# Payload.net
KiCad netlist of a schematic drawn in EAGLE
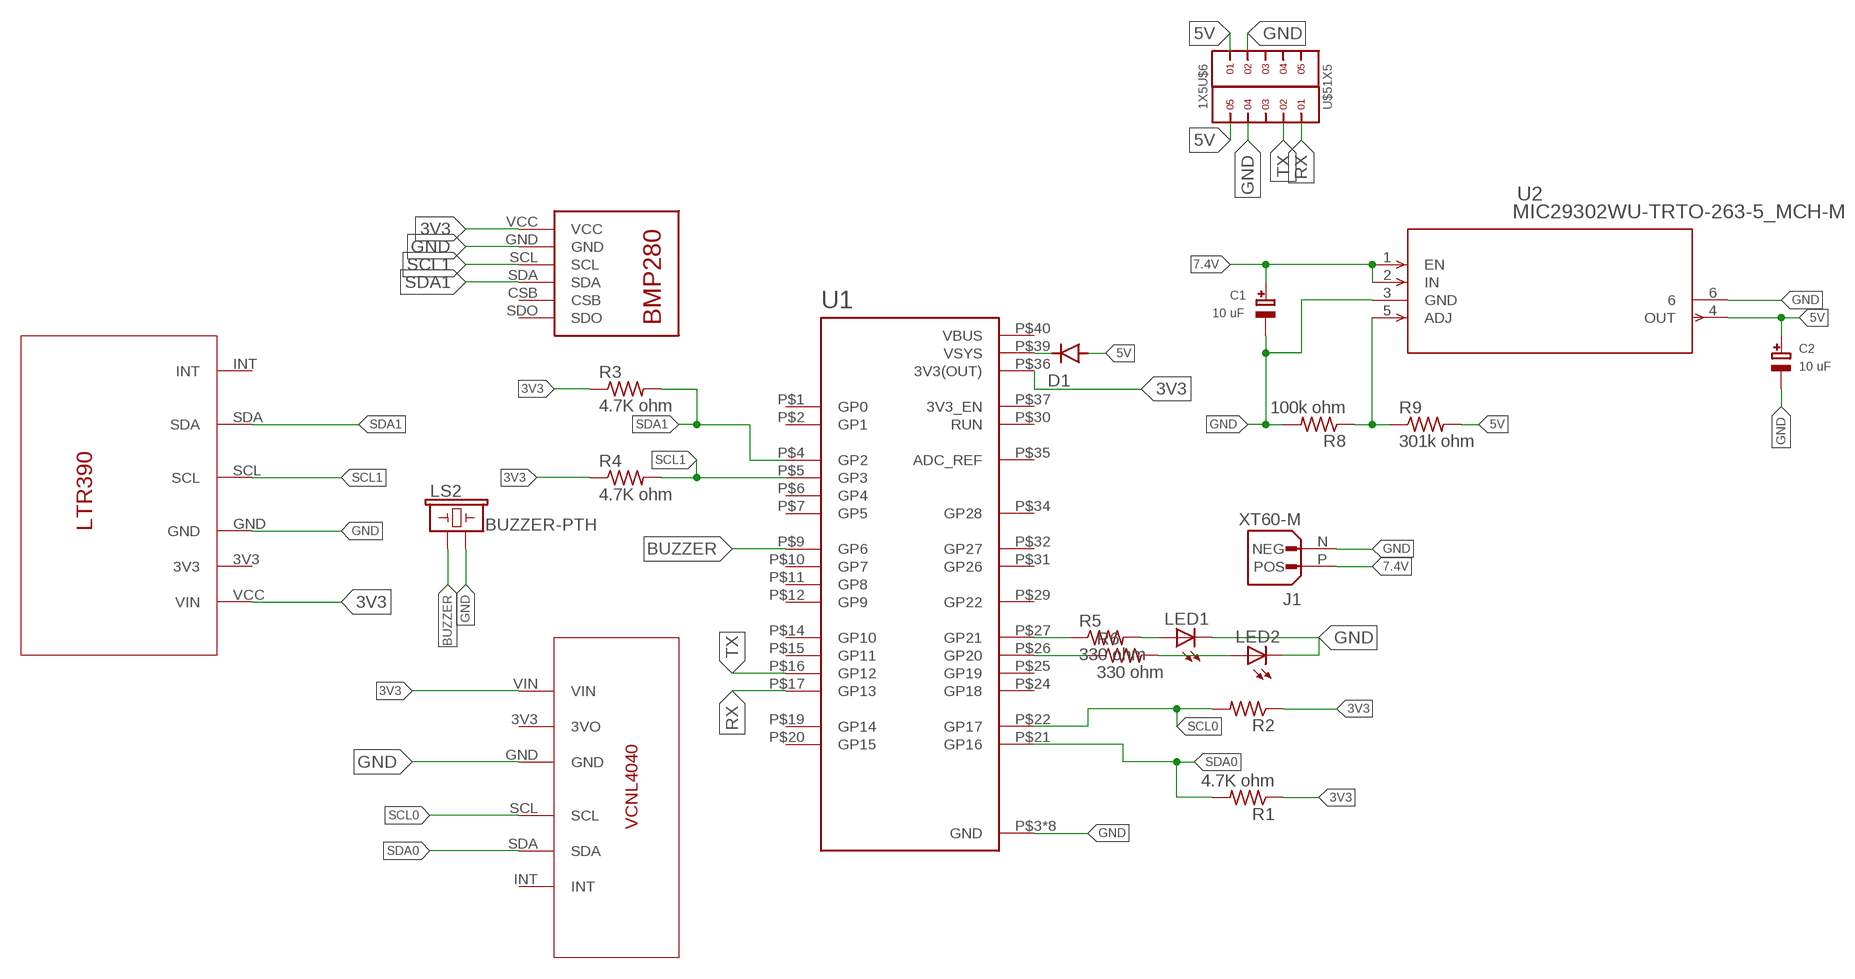
[diagram p0: schematic, sheet 1]

(export (version "E")
  (design (tool "Eeschema 10.0.6"))
  (components
    (comp (ref "C1")
      (value "10 uF")
      (footprint "eagle-import:EIA3216-18_A-W")
      (libsource (lib "eagle-import") (part "CAP_TANTALUMA/3216_WAVE"))
    )
    (comp (ref "C2")
      (value "10 uF")
      (footprint "eagle-import:EIA3216-18_A-W")
      (libsource (lib "eagle-import") (part "CAP_TANTALUMA/3216_WAVE"))
    )
    (comp (ref "D1")
      (value "1N4004")
      (footprint "eagle-import:DO41-10")
      (libsource (lib "eagle-import") (part "1N4004"))
    )
    (comp (ref "J1")
      (value "XT60-M")
      (footprint "eagle-import:AMASS_XT60-M")
      (fields (field (name "MF") "AMASS"))
      (libsource (lib "eagle-import") (part "XT60-M"))
    )
    (comp (ref "LED1")
      (value "LEDCHIPLED_1206")
      (footprint "eagle-import:CHIPLED_1206")
      (libsource (lib "eagle-import") (part "LEDCHIPLED_1206"))
    )
    (comp (ref "LED2")
      (value "LEDCHIPLED_1206")
      (footprint "eagle-import:CHIPLED_1206")
      (libsource (lib "eagle-import") (part "LEDCHIPLED_1206"))
    )
    (comp (ref "LS2")
      (value "BUZZER-PTH")
      (footprint "eagle-import:BUZZER-12MM")
      (libsource (lib "eagle-import") (part "BUZZER-PTH"))
    )
    (comp (ref "R1")
      (value "4.7K ohm")
      (footprint "eagle-import:R0805")
      (libsource (lib "eagle-import") (part "R-US_R0805"))
    )
    (comp (ref "R2")
      (value "4.7K ohm")
      (footprint "eagle-import:R0805")
      (libsource (lib "eagle-import") (part "R-US_R0805"))
    )
    (comp (ref "R3")
      (value "4.7K ohm")
      (footprint "eagle-import:R0805")
      (libsource (lib "eagle-import") (part "R-US_R0805"))
    )
    (comp (ref "R4")
      (value "4.7K ohm")
      (footprint "eagle-import:R0805")
      (libsource (lib "eagle-import") (part "R-US_R0805"))
    )
    (comp (ref "R5")
      (value "330 ohm")
      (footprint "eagle-import:R0805")
      (libsource (lib "eagle-import") (part "R-US_R0805"))
    )
    (comp (ref "R6")
      (value "330 ohm")
      (footprint "eagle-import:R0805")
      (libsource (lib "eagle-import") (part "R-US_R0805"))
    )
    (comp (ref "R8")
      (value "100k ohm")
      (footprint "eagle-import:R0805")
      (libsource (lib "eagle-import") (part "R-US_R0805"))
    )
    (comp (ref "R9")
      (value "301k ohm")
      (footprint "eagle-import:R0805")
      (libsource (lib "eagle-import") (part "R-US_R0805"))
    )
    (comp (ref "U$1")
      (value "VCNL4040")
      (footprint "eagle-import:VCNL4040")
      (libsource (lib "eagle-import") (part "VCNL4040"))
    )
    (comp (ref "U$3")
      (value "BMP280")
      (footprint "eagle-import:BMP280")
      (libsource (lib "eagle-import") (part "BMP280"))
    )
    (comp (ref "U$4")
      (value "LTR390")
      (footprint "eagle-import:LTR390")
      (libsource (lib "eagle-import") (part "LTR390"))
    )
    (comp (ref "U$5")
      (value "1X5")
      (footprint "eagle-import:1X5")
      (libsource (lib "eagle-import") (part "1X5"))
    )
    (comp (ref "U$6")
      (value "1X5")
      (footprint "eagle-import:1X5")
      (libsource (lib "eagle-import") (part "1X5"))
    )
    (comp (ref "U1")
      (value "RASPBERRY_PICO-NO_DEBUG")
      (footprint "eagle-import:PICO-PKG-NO_DEBUG")
      (libsource (lib "eagle-import") (part "RASPBERRY_PICO-NO_DEBUG"))
    )
    (comp (ref "U2")
      (value "MIC29302WU-TRTO-263-5_MCH-M")
      (footprint "eagle-import:TO-263-5_MCH-M")
      (fields
        (field (name "MANUFACTURER_PART_NUMBER") "MIC29302WU-TR")
        (field (name "COPYRIGHT") "Copyright (C) 2024 Ultra Librarian. All rights reserved.")
      )
      (libsource (lib "eagle-import") (part "MIC29302WU-TRTO-263-5_MCH-M"))
    )
  )
  (nets
    (net (code "1") (name "/VBUS") (class "Default")
      (node (ref "U1") (pin "P$40") (pinfunction "VBUS_P$40") (pintype "power_in"))
    )
    (net (code "2") (name "3V3") (class "Default")
      (node (ref "R1") (pin "1") (pinfunction "1_1") (pintype "passive"))
      (node (ref "R2") (pin "1") (pinfunction "1_1") (pintype "passive"))
      (node (ref "R3") (pin "1") (pinfunction "1_1") (pintype "passive"))
      (node (ref "R4") (pin "1") (pinfunction "1_1") (pintype "passive"))
      (node (ref "U$1") (pin "VIN") (pinfunction "VIN_VIN") (pintype "bidirectional"))
      (node (ref "U$3") (pin "VCC") (pinfunction "VCC_VCC") (pintype "bidirectional"))
      (node (ref "U$4") (pin "VCC") (pinfunction "VIN_VCC") (pintype "bidirectional"))
      (node (ref "U1") (pin "P$36") (pinfunction "3V3(OUT)_P$36") (pintype "power_in"))
    )
    (net (code "3") (name "5V") (class "Default")
      (node (ref "C2") (pin "+") (pinfunction "+_+") (pintype "passive"))
      (node (ref "D1") (pin "A") (pinfunction "A_A") (pintype "passive"))
      (node (ref "R9") (pin "2") (pinfunction "2_2") (pintype "passive"))
      (node (ref "U$5") (pin "5") (pinfunction "5_5") (pintype "bidirectional"))
      (node (ref "U$6") (pin "1") (pinfunction "1_1") (pintype "bidirectional"))
      (node (ref "U2") (pin "4") (pinfunction "OUT_4") (pintype "output"))
    )
    (net (code "4") (name "7.4V") (class "Default")
      (node (ref "C1") (pin "+") (pinfunction "+_+") (pintype "passive"))
      (node (ref "J1") (pin "P") (pinfunction "POS_P") (pintype "passive"))
      (node (ref "U2") (pin "1") (pinfunction "EN_1") (pintype "input"))
      (node (ref "U2") (pin "2") (pinfunction "IN_2") (pintype "input"))
    )
    (net (code "5") (name "BUZZER") (class "Default")
      (node (ref "LS2") (pin "+") (pinfunction "1_+") (pintype "passive"))
      (node (ref "U1") (pin "P$9") (pinfunction "GP6_P$9") (pintype "bidirectional"))
    )
    (net (code "6") (name "GND") (class "Default")
      (node (ref "C1") (pin "-") (pinfunction "-_-") (pintype "passive"))
      (node (ref "C2") (pin "-") (pinfunction "-_-") (pintype "passive"))
      (node (ref "J1") (pin "N") (pinfunction "NEG_N") (pintype "passive"))
      (node (ref "LED1") (pin "C") (pinfunction "C_C") (pintype "passive"))
      (node (ref "LED2") (pin "C") (pinfunction "C_C") (pintype "passive"))
      (node (ref "LS2") (pin "-") (pinfunction "2_-") (pintype "passive"))
      (node (ref "R8") (pin "2") (pinfunction "2_2") (pintype "passive"))
      (node (ref "U$1") (pin "GND") (pinfunction "GND_GND") (pintype "bidirectional"))
      (node (ref "U$3") (pin "GND") (pinfunction "GND_GND") (pintype "bidirectional"))
      (node (ref "U$4") (pin "GND") (pinfunction "GND_GND") (pintype "bidirectional"))
      (node (ref "U$5") (pin "4") (pinfunction "4_4") (pintype "bidirectional"))
      (node (ref "U$6") (pin "2") (pinfunction "2_2") (pintype "bidirectional"))
      (node (ref "U1") (pin "P$13") (pinfunction "GND_P$13") (pintype "power_in"))
      (node (ref "U1") (pin "P$18") (pinfunction "GND_P$18") (pintype "power_in"))
      (node (ref "U1") (pin "P$23") (pinfunction "GND_P$23") (pintype "power_in"))
      (node (ref "U1") (pin "P$28") (pinfunction "GND_P$28") (pintype "power_in"))
      (node (ref "U1") (pin "P$3") (pinfunction "GND_P$3") (pintype "power_in"))
      (node (ref "U1") (pin "P$33") (pinfunction "GND_P$33") (pintype "power_in"))
      (node (ref "U1") (pin "P$38") (pinfunction "GND_P$38") (pintype "power_in"))
      (node (ref "U1") (pin "P$8") (pinfunction "GND_P$8") (pintype "power_in"))
      (node (ref "U2") (pin "3") (pinfunction "GND_3") (pintype "power_in"))
      (node (ref "U2") (pin "6") (pinfunction "6_6") (pintype "passive"))
    )
    (net (code "7") (name "Net-(LED1-PadA)") (class "Default")
      (node (ref "LED1") (pin "A") (pinfunction "A_A") (pintype "passive"))
      (node (ref "R5") (pin "2") (pinfunction "2_2") (pintype "passive"))
    )
    (net (code "8") (name "Net-(LED2-PadA)") (class "Default")
      (node (ref "LED2") (pin "A") (pinfunction "A_A") (pintype "passive"))
      (node (ref "R6") (pin "2") (pinfunction "2_2") (pintype "passive"))
    )
    (net (code "9") (name "Net-(U1-GP20)") (class "Default")
      (node (ref "R6") (pin "1") (pinfunction "1_1") (pintype "passive"))
      (node (ref "U1") (pin "P$26") (pinfunction "GP20_P$26") (pintype "bidirectional"))
    )
    (net (code "10") (name "Net-(U1-GP21)") (class "Default")
      (node (ref "R5") (pin "1") (pinfunction "1_1") (pintype "passive"))
      (node (ref "U1") (pin "P$27") (pinfunction "GP21_P$27") (pintype "bidirectional"))
    )
    (net (code "11") (name "Net-(U1-VSYS)") (class "Default")
      (node (ref "D1") (pin "C") (pinfunction "C_C") (pintype "passive"))
      (node (ref "U1") (pin "P$39") (pinfunction "VSYS_P$39") (pintype "power_in"))
    )
    (net (code "12") (name "Net-(U2-ADJ)") (class "Default")
      (node (ref "R8") (pin "1") (pinfunction "1_1") (pintype "passive"))
      (node (ref "R9") (pin "1") (pinfunction "1_1") (pintype "passive"))
      (node (ref "U2") (pin "5") (pinfunction "ADJ_5") (pintype "input"))
    )
    (net (code "13") (name "RX") (class "Default")
      (node (ref "U$5") (pin "1") (pinfunction "1_1") (pintype "bidirectional"))
      (node (ref "U1") (pin "P$17") (pinfunction "GP13_P$17") (pintype "bidirectional"))
    )
    (net (code "14") (name "SCL0") (class "Default")
      (node (ref "R2") (pin "2") (pinfunction "2_2") (pintype "passive"))
      (node (ref "U$1") (pin "SCL") (pinfunction "SCL_SCL") (pintype "bidirectional"))
      (node (ref "U1") (pin "P$22") (pinfunction "GP17_P$22") (pintype "bidirectional"))
    )
    (net (code "15") (name "SCL1") (class "Default")
      (node (ref "R4") (pin "2") (pinfunction "2_2") (pintype "passive"))
      (node (ref "U$3") (pin "SCL") (pinfunction "SCL_SCL") (pintype "bidirectional"))
      (node (ref "U$4") (pin "SCL") (pinfunction "SCL_SCL") (pintype "bidirectional"))
      (node (ref "U1") (pin "P$5") (pinfunction "GP3_P$5") (pintype "bidirectional"))
    )
    (net (code "16") (name "SDA0") (class "Default")
      (node (ref "R1") (pin "2") (pinfunction "2_2") (pintype "passive"))
      (node (ref "U$1") (pin "SDA") (pinfunction "SDA_SDA") (pintype "bidirectional"))
      (node (ref "U1") (pin "P$21") (pinfunction "GP16_P$21") (pintype "bidirectional"))
    )
    (net (code "17") (name "SDA1") (class "Default")
      (node (ref "R3") (pin "2") (pinfunction "2_2") (pintype "passive"))
      (node (ref "U$3") (pin "SDA") (pinfunction "SDA_SDA") (pintype "bidirectional"))
      (node (ref "U$4") (pin "SDA") (pinfunction "SDA_SDA") (pintype "bidirectional"))
      (node (ref "U1") (pin "P$4") (pinfunction "GP2_P$4") (pintype "bidirectional"))
    )
    (net (code "18") (name "TX") (class "Default")
      (node (ref "U$5") (pin "2") (pinfunction "2_2") (pintype "bidirectional"))
      (node (ref "U1") (pin "P$16") (pinfunction "GP12_P$16") (pintype "bidirectional"))
    )
    (net (code "19") (name "unconnected-(U$1-3VO-Pad3V3)") (class "Default")
      (node (ref "U$1") (pin "3V3") (pinfunction "3VO_3V3") (pintype "bidirectional"))
    )
    (net (code "20") (name "unconnected-(U$1-PadINT)") (class "Default")
      (node (ref "U$1") (pin "INT") (pinfunction "INT_INT") (pintype "bidirectional"))
    )
    (net (code "21") (name "unconnected-(U$3-PadCSB)") (class "Default")
      (node (ref "U$3") (pin "CSB") (pinfunction "CSB_CSB") (pintype "bidirectional"))
    )
    (net (code "22") (name "unconnected-(U$3-PadSDO)") (class "Default")
      (node (ref "U$3") (pin "SDO") (pinfunction "SDO_SDO") (pintype "bidirectional"))
    )
    (net (code "23") (name "unconnected-(U$4-Pad3V3)") (class "Default")
      (node (ref "U$4") (pin "3V3") (pinfunction "3V3_3V3") (pintype "bidirectional"))
    )
    (net (code "24") (name "unconnected-(U$4-PadINT)") (class "Default")
      (node (ref "U$4") (pin "INT") (pinfunction "INT_INT") (pintype "bidirectional"))
    )
    (net (code "25") (name "unconnected-(U$5-Pad3)") (class "Default")
      (node (ref "U$5") (pin "3") (pinfunction "3_3") (pintype "bidirectional"))
    )
    (net (code "26") (name "unconnected-(U$6-Pad3)") (class "Default")
      (node (ref "U$6") (pin "3") (pinfunction "3_3") (pintype "bidirectional"))
    )
    (net (code "27") (name "unconnected-(U$6-Pad4)") (class "Default")
      (node (ref "U$6") (pin "4") (pinfunction "4_4") (pintype "bidirectional"))
    )
    (net (code "28") (name "unconnected-(U$6-Pad5)") (class "Default")
      (node (ref "U$6") (pin "5") (pinfunction "5_5") (pintype "bidirectional"))
    )
    (net (code "29") (name "unconnected-(U1-3V3_EN-PadP$37)") (class "Default")
      (node (ref "U1") (pin "P$37") (pinfunction "3V3_EN_P$37") (pintype "input"))
    )
    (net (code "30") (name "unconnected-(U1-ADC_REF-PadP$35)") (class "Default")
      (node (ref "U1") (pin "P$35") (pinfunction "ADC_REF_P$35") (pintype "input"))
    )
    (net (code "31") (name "unconnected-(U1-GP0-PadP$1)") (class "Default")
      (node (ref "U1") (pin "P$1") (pinfunction "GP0_P$1") (pintype "bidirectional"))
    )
    (net (code "32") (name "unconnected-(U1-GP1-PadP$2)") (class "Default")
      (node (ref "U1") (pin "P$2") (pinfunction "GP1_P$2") (pintype "bidirectional"))
    )
    (net (code "33") (name "unconnected-(U1-GP4-PadP$6)") (class "Default")
      (node (ref "U1") (pin "P$6") (pinfunction "GP4_P$6") (pintype "bidirectional"))
    )
    (net (code "34") (name "unconnected-(U1-GP5-PadP$7)") (class "Default")
      (node (ref "U1") (pin "P$7") (pinfunction "GP5_P$7") (pintype "bidirectional"))
    )
    (net (code "35") (name "unconnected-(U1-GP7-PadP$10)") (class "Default")
      (node (ref "U1") (pin "P$10") (pinfunction "GP7_P$10") (pintype "bidirectional"))
    )
    (net (code "36") (name "unconnected-(U1-GP8-PadP$11)") (class "Default")
      (node (ref "U1") (pin "P$11") (pinfunction "GP8_P$11") (pintype "bidirectional"))
    )
    (net (code "37") (name "unconnected-(U1-GP9-PadP$12)") (class "Default")
      (node (ref "U1") (pin "P$12") (pinfunction "GP9_P$12") (pintype "bidirectional"))
    )
    (net (code "38") (name "unconnected-(U1-GP10-PadP$14)") (class "Default")
      (node (ref "U1") (pin "P$14") (pinfunction "GP10_P$14") (pintype "bidirectional"))
    )
    (net (code "39") (name "unconnected-(U1-GP11-PadP$15)") (class "Default")
      (node (ref "U1") (pin "P$15") (pinfunction "GP11_P$15") (pintype "bidirectional"))
    )
    (net (code "40") (name "unconnected-(U1-GP14-PadP$19)") (class "Default")
      (node (ref "U1") (pin "P$19") (pinfunction "GP14_P$19") (pintype "bidirectional"))
    )
    (net (code "41") (name "unconnected-(U1-GP15-PadP$20)") (class "Default")
      (node (ref "U1") (pin "P$20") (pinfunction "GP15_P$20") (pintype "bidirectional"))
    )
    (net (code "42") (name "unconnected-(U1-GP18-PadP$24)") (class "Default")
      (node (ref "U1") (pin "P$24") (pinfunction "GP18_P$24") (pintype "bidirectional"))
    )
    (net (code "43") (name "unconnected-(U1-GP19-PadP$25)") (class "Default")
      (node (ref "U1") (pin "P$25") (pinfunction "GP19_P$25") (pintype "bidirectional"))
    )
    (net (code "44") (name "unconnected-(U1-GP22-PadP$29)") (class "Default")
      (node (ref "U1") (pin "P$29") (pinfunction "GP22_P$29") (pintype "bidirectional"))
    )
    (net (code "45") (name "unconnected-(U1-GP26-PadP$31)") (class "Default")
      (node (ref "U1") (pin "P$31") (pinfunction "GP26_P$31") (pintype "bidirectional"))
    )
    (net (code "46") (name "unconnected-(U1-GP27-PadP$32)") (class "Default")
      (node (ref "U1") (pin "P$32") (pinfunction "GP27_P$32") (pintype "bidirectional"))
    )
    (net (code "47") (name "unconnected-(U1-GP28-PadP$34)") (class "Default")
      (node (ref "U1") (pin "P$34") (pinfunction "GP28_P$34") (pintype "bidirectional"))
    )
    (net (code "48") (name "unconnected-(U1-RUN-PadP$30)") (class "Default")
      (node (ref "U1") (pin "P$30") (pinfunction "RUN_P$30") (pintype "input"))
    )
  )
)
